# Level_Shifters.net
KiCad netlist of a schematic drawn in Altium Designer
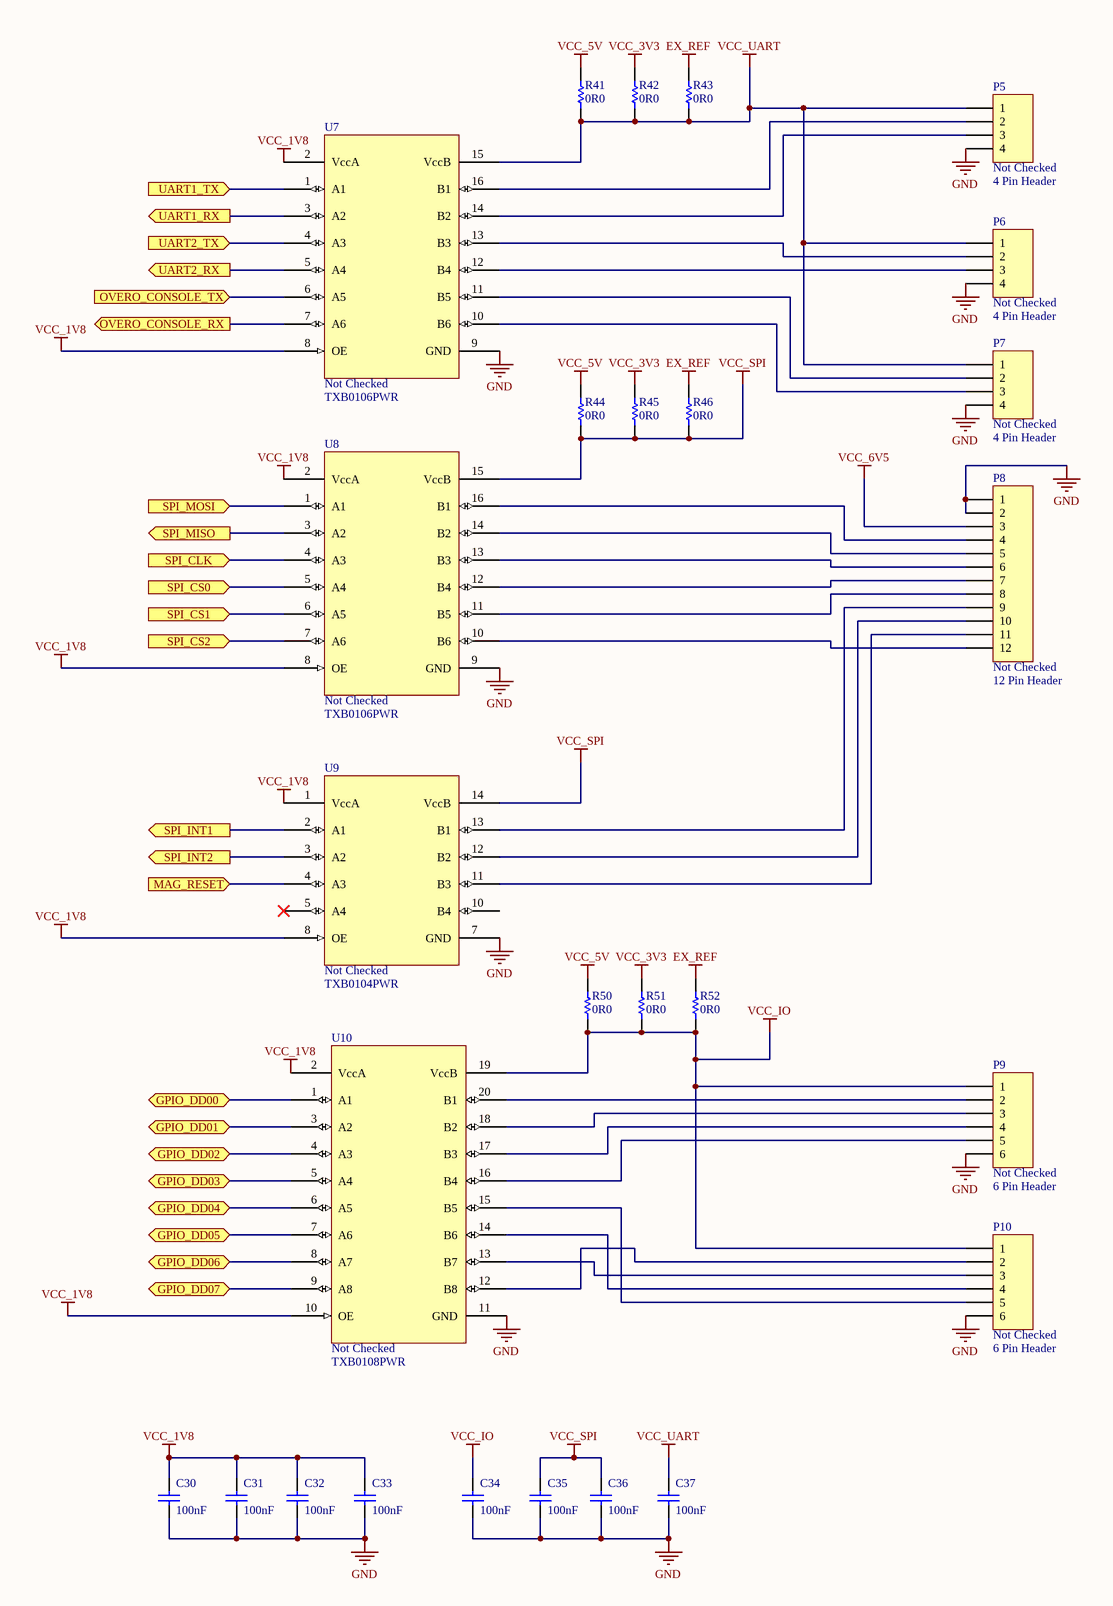
[diagram p0: Level Shifters.SchDoc]

(export (version "E")
  (design (tool "Eeschema 10.0.6"))
  (components
    (comp (ref "C30")
      (value "100nF")
      (footprint "GRC PCB library:0603")
      (description "CAP CER .10UF 50V X5R 0603")
      (fields (field (name "MANUFACTURER") "Taiyo Yuden"))
      (libsource (lib "GRC sch library") (part "CP_100nF 0603"))
    )
    (comp (ref "C31")
      (value "100nF")
      (footprint "GRC PCB library:0603")
      (description "CAP CER .10UF 50V X5R 0603")
      (fields (field (name "MANUFACTURER") "Taiyo Yuden"))
      (libsource (lib "GRC sch library") (part "CP_100nF 0603"))
    )
    (comp (ref "C32")
      (value "100nF")
      (footprint "GRC PCB library:0603")
      (description "CAP CER .10UF 50V X5R 0603")
      (fields (field (name "MANUFACTURER") "Taiyo Yuden"))
      (libsource (lib "GRC sch library") (part "CP_100nF 0603"))
    )
    (comp (ref "C33")
      (value "100nF")
      (footprint "GRC PCB library:0603")
      (description "CAP CER .10UF 50V X5R 0603")
      (fields (field (name "MANUFACTURER") "Taiyo Yuden"))
      (libsource (lib "GRC sch library") (part "CP_100nF 0603"))
    )
    (comp (ref "C34")
      (value "100nF")
      (footprint "GRC PCB library:0603")
      (description "CAP CER .10UF 50V X5R 0603")
      (fields (field (name "MANUFACTURER") "Taiyo Yuden"))
      (libsource (lib "GRC sch library") (part "CP_100nF 0603"))
    )
    (comp (ref "C35")
      (value "100nF")
      (footprint "GRC PCB library:0603")
      (description "CAP CER .10UF 50V X5R 0603")
      (fields (field (name "MANUFACTURER") "Taiyo Yuden"))
      (libsource (lib "GRC sch library") (part "CP_100nF 0603"))
    )
    (comp (ref "C36")
      (value "100nF")
      (footprint "GRC PCB library:0603")
      (description "CAP CER .10UF 50V X5R 0603")
      (fields (field (name "MANUFACTURER") "Taiyo Yuden"))
      (libsource (lib "GRC sch library") (part "CP_100nF 0603"))
    )
    (comp (ref "C37")
      (value "100nF")
      (footprint "GRC PCB library:0603")
      (description "CAP CER .10UF 50V X5R 0603")
      (fields (field (name "MANUFACTURER") "Taiyo Yuden"))
      (libsource (lib "GRC sch library") (part "CP_100nF 0603"))
    )
    (comp (ref "P5")
      (value "4 Pin Header")
      (footprint "CONN_4X1_SMT_RA_1.25MM")
      (description "CONN HDR VERT 4POS .100\" SNGL")
      (fields (field (name "MANUFACTURER") "Molex") (field (name "VERIFY") "Not Checked"))
      (libsource (lib "checked") (part "JP_4PIN HDR_SMT_RA_MOLEX"))
    )
    (comp (ref "P6")
      (value "4 Pin Header")
      (footprint "CONN_4X1_SMT_RA_1.25MM")
      (description "CONN HDR VERT 4POS .100\" SNGL")
      (fields (field (name "MANUFACTURER") "Molex") (field (name "VERIFY") "Not Checked"))
      (libsource (lib "checked") (part "JP_4PIN HDR_SMT_RA_MOLEX"))
    )
    (comp (ref "P7")
      (value "4 Pin Header")
      (footprint "CONN_4X1_SMT_RA_1.25MM")
      (description "CONN HDR VERT 4POS .100\" SNGL")
      (fields (field (name "MANUFACTURER") "Molex") (field (name "VERIFY") "Not Checked"))
      (libsource (lib "checked") (part "JP_4PIN HDR_SMT_RA_MOLEX"))
    )
    (comp (ref "P8")
      (value "12 Pin Header")
      (footprint "CONN_12X1_SMT_RA_1.25MM")
      (description "CONN HDR VERT 12POS .100\" SNGL")
      (fields (field (name "MANUFACTURER") "Molex") (field (name "VERIFY") "Not Checked"))
      (libsource (lib "checked") (part "JP_12PIN HDR_SMT_RA_MOLEX"))
    )
    (comp (ref "P9")
      (value "6 Pin Header")
      (footprint "CONN_6X1_SMT_RA_1.25MM")
      (description "CONN HDR VERT 6POS .100\" SNGL")
      (fields (field (name "MANUFACTURER") "Molex") (field (name "VERIFY") "Not Checked"))
      (libsource (lib "checked") (part "JP_6PIN HDR_SMT_RA_MOLEX"))
    )
    (comp (ref "P10")
      (value "6 Pin Header")
      (footprint "CONN_6X1_SMT_RA_1.25MM")
      (description "CONN HDR VERT 6POS .100\" SNGL")
      (fields (field (name "MANUFACTURER") "Molex") (field (name "VERIFY") "Not Checked"))
      (libsource (lib "checked") (part "JP_6PIN HDR_SMT_RA_MOLEX"))
    )
    (comp (ref "R41")
      (value "0R0")
      (footprint "GRC PCB library:0603")
      (description "RES 0.0 OHM 1/10W 5% 0603 SMD")
      (fields (field (name "MANUFACTURER") "Rohm"))
      (libsource (lib "GRC sch library") (part "RS_0R0 0603"))
    )
    (comp (ref "R42")
      (value "0R0")
      (footprint "GRC PCB library:0603")
      (description "RES 0.0 OHM 1/10W 5% 0603 SMD")
      (fields (field (name "MANUFACTURER") "Rohm"))
      (libsource (lib "GRC sch library") (part "RS_0R0 0603"))
    )
    (comp (ref "R43")
      (value "0R0")
      (footprint "GRC PCB library:0603")
      (description "RES 0.0 OHM 1/10W 5% 0603 SMD")
      (fields (field (name "MANUFACTURER") "Rohm"))
      (libsource (lib "GRC sch library") (part "RS_0R0 0603"))
    )
    (comp (ref "R44")
      (value "0R0")
      (footprint "GRC PCB library:0603")
      (description "RES 0.0 OHM 1/10W 5% 0603 SMD")
      (fields (field (name "MANUFACTURER") "Rohm"))
      (libsource (lib "GRC sch library") (part "RS_0R0 0603"))
    )
    (comp (ref "R45")
      (value "0R0")
      (footprint "GRC PCB library:0603")
      (description "RES 0.0 OHM 1/10W 5% 0603 SMD")
      (fields (field (name "MANUFACTURER") "Rohm"))
      (libsource (lib "GRC sch library") (part "RS_0R0 0603"))
    )
    (comp (ref "R46")
      (value "0R0")
      (footprint "GRC PCB library:0603")
      (description "RES 0.0 OHM 1/10W 5% 0603 SMD")
      (fields (field (name "MANUFACTURER") "Rohm"))
      (libsource (lib "GRC sch library") (part "RS_0R0 0603"))
    )
    (comp (ref "R50")
      (value "0R0")
      (footprint "GRC PCB library:0603")
      (description "RES 0.0 OHM 1/10W 5% 0603 SMD")
      (fields (field (name "MANUFACTURER") "Rohm"))
      (libsource (lib "GRC sch library") (part "RS_0R0 0603"))
    )
    (comp (ref "R51")
      (value "0R0")
      (footprint "GRC PCB library:0603")
      (description "RES 0.0 OHM 1/10W 5% 0603 SMD")
      (fields (field (name "MANUFACTURER") "Rohm"))
      (libsource (lib "GRC sch library") (part "RS_0R0 0603"))
    )
    (comp (ref "R52")
      (value "0R0")
      (footprint "GRC PCB library:0603")
      (description "RES 0.0 OHM 1/10W 5% 0603 SMD")
      (fields (field (name "MANUFACTURER") "Rohm"))
      (libsource (lib "GRC sch library") (part "RS_0R0 0603"))
    )
    (comp (ref "U7")
      (value "TXB0106PWR")
      (footprint "TSSOP-16_PW")
      (description "IC VOLT-LEVEL TRANSLATOR 16TSSOP")
      (fields
        (field (name "MANUFACTURER") "Texas Instruments")
        (field (name "VERIFY") "Not Checked")
        (field (name "Comment") "IC_TXB0106PWR")
      )
      (libsource (lib "checked") (part "IC_TXB0106PWR"))
    )
    (comp (ref "U8")
      (value "TXB0106PWR")
      (footprint "TSSOP-16_PW")
      (description "IC VOLT-LEVEL TRANSLATOR 16TSSOP")
      (fields
        (field (name "MANUFACTURER") "Texas Instruments")
        (field (name "VERIFY") "Not Checked")
        (field (name "Comment") "IC_TXB0106PWR")
      )
      (libsource (lib "checked") (part "IC_TXB0106PWR"))
    )
    (comp (ref "U9")
      (value "TXB0104PWR")
      (footprint "TSSOP-14_PW")
      (description "IC VOLT-LEVEL TRANSLATOR 14TSSOP")
      (fields
        (field (name "MANUFACTURER") "Texas Instruments")
        (field (name "VERIFY") "Not Checked")
        (field (name "Comment") "IC_TXB0104PWR")
      )
      (libsource (lib "checked") (part "IC_TXB0104PWR"))
    )
    (comp (ref "U10")
      (value "TXB0108PWR")
      (footprint "TSSOP-20_PW")
      (description "IC VOLT-LEVEL TRANSLATOR 20TSSOP")
      (fields
        (field (name "MANUFACTURER") "Texas Instruments")
        (field (name "VERIFY") "Not Checked")
        (field (name "Comment") "IC_TXB0108PWR")
      )
      (libsource (lib "checked") (part "IC_TXB0108PWR"))
    )
  )
  (nets
    (net (code "1") (name "/GPIO_DD00") (class "Default")
      (node (ref "U10") (pin "1") (pinfunction "A1_1") (pintype "bidirectional"))
    )
    (net (code "2") (name "/GPIO_DD01") (class "Default")
      (node (ref "U10") (pin "3") (pinfunction "A2_3") (pintype "bidirectional"))
    )
    (net (code "3") (name "/GPIO_DD02") (class "Default")
      (node (ref "U10") (pin "4") (pinfunction "A3_4") (pintype "bidirectional"))
    )
    (net (code "4") (name "/GPIO_DD03") (class "Default")
      (node (ref "U10") (pin "5") (pinfunction "A4_5") (pintype "bidirectional"))
    )
    (net (code "5") (name "/GPIO_DD04") (class "Default")
      (node (ref "U10") (pin "6") (pinfunction "A5_6") (pintype "bidirectional"))
    )
    (net (code "6") (name "/GPIO_DD05") (class "Default")
      (node (ref "U10") (pin "7") (pinfunction "A6_7") (pintype "bidirectional"))
    )
    (net (code "7") (name "/GPIO_DD06") (class "Default")
      (node (ref "U10") (pin "8") (pinfunction "A7_8") (pintype "bidirectional"))
    )
    (net (code "8") (name "/GPIO_DD07") (class "Default")
      (node (ref "U10") (pin "9") (pinfunction "A8_9") (pintype "bidirectional"))
    )
    (net (code "9") (name "/MAG_RESET") (class "Default")
      (node (ref "U9") (pin "4") (pinfunction "A3_4") (pintype "bidirectional"))
    )
    (net (code "10") (name "/OVERO_CONSOLE_RX") (class "Default")
      (node (ref "U7") (pin "7") (pinfunction "A6_7") (pintype "bidirectional"))
    )
    (net (code "11") (name "/OVERO_CONSOLE_TX") (class "Default")
      (node (ref "U7") (pin "6") (pinfunction "A5_6") (pintype "bidirectional"))
    )
    (net (code "12") (name "/SPI_CLK") (class "Default")
      (node (ref "U8") (pin "4") (pinfunction "A3_4") (pintype "bidirectional"))
    )
    (net (code "13") (name "/SPI_CS0") (class "Default")
      (node (ref "U8") (pin "5") (pinfunction "A4_5") (pintype "bidirectional"))
    )
    (net (code "14") (name "/SPI_CS1") (class "Default")
      (node (ref "U8") (pin "6") (pinfunction "A5_6") (pintype "bidirectional"))
    )
    (net (code "15") (name "/SPI_CS2") (class "Default")
      (node (ref "U8") (pin "7") (pinfunction "A6_7") (pintype "bidirectional"))
    )
    (net (code "16") (name "/SPI_INT1") (class "Default")
      (node (ref "U9") (pin "2") (pinfunction "A1_2") (pintype "bidirectional"))
    )
    (net (code "17") (name "/SPI_INT2") (class "Default")
      (node (ref "U9") (pin "3") (pinfunction "A2_3") (pintype "bidirectional"))
    )
    (net (code "18") (name "/SPI_MISO") (class "Default")
      (node (ref "U8") (pin "3") (pinfunction "A2_3") (pintype "bidirectional"))
    )
    (net (code "19") (name "/SPI_MOSI") (class "Default")
      (node (ref "U8") (pin "1") (pinfunction "A1_1") (pintype "bidirectional"))
    )
    (net (code "20") (name "/UART1_RX") (class "Default")
      (node (ref "U7") (pin "3") (pinfunction "A2_3") (pintype "bidirectional"))
    )
    (net (code "21") (name "/UART1_TX") (class "Default")
      (node (ref "U7") (pin "1") (pinfunction "A1_1") (pintype "bidirectional"))
    )
    (net (code "22") (name "/UART2_RX") (class "Default")
      (node (ref "U7") (pin "5") (pinfunction "A4_5") (pintype "bidirectional"))
    )
    (net (code "23") (name "/UART2_TX") (class "Default")
      (node (ref "U7") (pin "4") (pinfunction "A3_4") (pintype "bidirectional"))
    )
    (net (code "24") (name "EX_REF") (class "Default")
      (node (ref "R43") (pin "1") (pinfunction "1_1") (pintype "passive"))
      (node (ref "R46") (pin "1") (pinfunction "1_1") (pintype "passive"))
      (node (ref "R52") (pin "1") (pinfunction "1_1") (pintype "passive"))
    )
    (net (code "25") (name "GND") (class "Default")
      (node (ref "C30") (pin "1") (pinfunction "1_1") (pintype "passive"))
      (node (ref "C31") (pin "1") (pinfunction "1_1") (pintype "passive"))
      (node (ref "C32") (pin "1") (pinfunction "1_1") (pintype "passive"))
      (node (ref "C33") (pin "1") (pinfunction "1_1") (pintype "passive"))
      (node (ref "C34") (pin "1") (pinfunction "1_1") (pintype "passive"))
      (node (ref "C35") (pin "1") (pinfunction "1_1") (pintype "passive"))
      (node (ref "C36") (pin "1") (pinfunction "1_1") (pintype "passive"))
      (node (ref "C37") (pin "1") (pinfunction "1_1") (pintype "passive"))
      (node (ref "P10") (pin "6") (pinfunction "6_6") (pintype "passive"))
      (node (ref "P5") (pin "4") (pinfunction "4_4") (pintype "passive"))
      (node (ref "P6") (pin "4") (pinfunction "4_4") (pintype "passive"))
      (node (ref "P7") (pin "4") (pinfunction "4_4") (pintype "passive"))
      (node (ref "P8") (pin "1") (pinfunction "1_1") (pintype "passive"))
      (node (ref "P8") (pin "2") (pinfunction "2_2") (pintype "passive"))
      (node (ref "P9") (pin "6") (pinfunction "6_6") (pintype "passive"))
      (node (ref "U10") (pin "11") (pinfunction "GND_11") (pintype "power_in"))
      (node (ref "U7") (pin "9") (pinfunction "GND_9") (pintype "power_in"))
      (node (ref "U8") (pin "9") (pinfunction "GND_9") (pintype "power_in"))
      (node (ref "U9") (pin "7") (pinfunction "GND_7") (pintype "power_in"))
    )
    (net (code "26") (name "Net-(U7-B1)") (class "Default")
      (node (ref "P5") (pin "2") (pinfunction "2_2") (pintype "passive"))
      (node (ref "U7") (pin "16") (pinfunction "B1_16") (pintype "bidirectional"))
    )
    (net (code "27") (name "Net-(U7-B2)") (class "Default")
      (node (ref "P5") (pin "3") (pinfunction "3_3") (pintype "passive"))
      (node (ref "U7") (pin "14") (pinfunction "B2_14") (pintype "bidirectional"))
    )
    (net (code "28") (name "Net-(U7-B3)") (class "Default")
      (node (ref "P6") (pin "2") (pinfunction "2_2") (pintype "passive"))
      (node (ref "U7") (pin "13") (pinfunction "B3_13") (pintype "bidirectional"))
    )
    (net (code "29") (name "Net-(U7-B4)") (class "Default")
      (node (ref "P6") (pin "3") (pinfunction "3_3") (pintype "passive"))
      (node (ref "U7") (pin "12") (pinfunction "B4_12") (pintype "bidirectional"))
    )
    (net (code "30") (name "Net-(U7-B5)") (class "Default")
      (node (ref "P7") (pin "2") (pinfunction "2_2") (pintype "passive"))
      (node (ref "U7") (pin "11") (pinfunction "B5_11") (pintype "bidirectional"))
    )
    (net (code "31") (name "Net-(U7-B6)") (class "Default")
      (node (ref "P7") (pin "3") (pinfunction "3_3") (pintype "passive"))
      (node (ref "U7") (pin "10") (pinfunction "B6_10") (pintype "bidirectional"))
    )
    (net (code "32") (name "Net-(U8-B1)") (class "Default")
      (node (ref "P8") (pin "4") (pinfunction "4_4") (pintype "passive"))
      (node (ref "U8") (pin "16") (pinfunction "B1_16") (pintype "bidirectional"))
    )
    (net (code "33") (name "Net-(U8-B2)") (class "Default")
      (node (ref "P8") (pin "5") (pinfunction "5_5") (pintype "passive"))
      (node (ref "U8") (pin "14") (pinfunction "B2_14") (pintype "bidirectional"))
    )
    (net (code "34") (name "Net-(U8-B3)") (class "Default")
      (node (ref "P8") (pin "6") (pinfunction "6_6") (pintype "passive"))
      (node (ref "U8") (pin "13") (pinfunction "B3_13") (pintype "bidirectional"))
    )
    (net (code "35") (name "Net-(U8-B4)") (class "Default")
      (node (ref "P8") (pin "7") (pinfunction "7_7") (pintype "passive"))
      (node (ref "U8") (pin "12") (pinfunction "B4_12") (pintype "bidirectional"))
    )
    (net (code "36") (name "Net-(U8-B5)") (class "Default")
      (node (ref "P8") (pin "8") (pinfunction "8_8") (pintype "passive"))
      (node (ref "U8") (pin "11") (pinfunction "B5_11") (pintype "bidirectional"))
    )
    (net (code "37") (name "Net-(U8-B6)") (class "Default")
      (node (ref "P8") (pin "12") (pinfunction "12_12") (pintype "passive"))
      (node (ref "U8") (pin "10") (pinfunction "B6_10") (pintype "bidirectional"))
    )
    (net (code "38") (name "Net-(U9-B1)") (class "Default")
      (node (ref "P8") (pin "9") (pinfunction "9_9") (pintype "passive"))
      (node (ref "U9") (pin "13") (pinfunction "B1_13") (pintype "bidirectional"))
    )
    (net (code "39") (name "Net-(U9-B2)") (class "Default")
      (node (ref "P8") (pin "10") (pinfunction "10_10") (pintype "passive"))
      (node (ref "U9") (pin "12") (pinfunction "B2_12") (pintype "bidirectional"))
    )
    (net (code "40") (name "Net-(U9-B3)") (class "Default")
      (node (ref "P8") (pin "11") (pinfunction "11_11") (pintype "passive"))
      (node (ref "U9") (pin "11") (pinfunction "B3_11") (pintype "bidirectional"))
    )
    (net (code "41") (name "Net-(U10-B1)") (class "Default")
      (node (ref "P9") (pin "2") (pinfunction "2_2") (pintype "passive"))
      (node (ref "U10") (pin "20") (pinfunction "B1_20") (pintype "bidirectional"))
    )
    (net (code "42") (name "Net-(U10-B2)") (class "Default")
      (node (ref "P9") (pin "3") (pinfunction "3_3") (pintype "passive"))
      (node (ref "U10") (pin "18") (pinfunction "B2_18") (pintype "bidirectional"))
    )
    (net (code "43") (name "Net-(U10-B3)") (class "Default")
      (node (ref "P9") (pin "4") (pinfunction "4_4") (pintype "passive"))
      (node (ref "U10") (pin "17") (pinfunction "B3_17") (pintype "bidirectional"))
    )
    (net (code "44") (name "Net-(U10-B4)") (class "Default")
      (node (ref "P9") (pin "5") (pinfunction "5_5") (pintype "passive"))
      (node (ref "U10") (pin "16") (pinfunction "B4_16") (pintype "bidirectional"))
    )
    (net (code "45") (name "Net-(U10-B5)") (class "Default")
      (node (ref "P10") (pin "5") (pinfunction "5_5") (pintype "passive"))
      (node (ref "U10") (pin "15") (pinfunction "B5_15") (pintype "bidirectional"))
    )
    (net (code "46") (name "Net-(U10-B6)") (class "Default")
      (node (ref "P10") (pin "4") (pinfunction "4_4") (pintype "passive"))
      (node (ref "U10") (pin "14") (pinfunction "B6_14") (pintype "bidirectional"))
    )
    (net (code "47") (name "Net-(U10-B7)") (class "Default")
      (node (ref "P10") (pin "3") (pinfunction "3_3") (pintype "passive"))
      (node (ref "U10") (pin "13") (pinfunction "B7_13") (pintype "bidirectional"))
    )
    (net (code "48") (name "Net-(U10-B8)") (class "Default")
      (node (ref "P10") (pin "2") (pinfunction "2_2") (pintype "passive"))
      (node (ref "U10") (pin "12") (pinfunction "B8_12") (pintype "bidirectional"))
    )
    (net (code "49") (name "VCC_1V8") (class "Default")
      (node (ref "C30") (pin "2") (pinfunction "2_2") (pintype "passive"))
      (node (ref "C31") (pin "2") (pinfunction "2_2") (pintype "passive"))
      (node (ref "C32") (pin "2") (pinfunction "2_2") (pintype "passive"))
      (node (ref "C33") (pin "2") (pinfunction "2_2") (pintype "passive"))
      (node (ref "U10") (pin "10") (pinfunction "OE_10") (pintype "input"))
      (node (ref "U10") (pin "2") (pinfunction "VccA_2") (pintype "power_in"))
      (node (ref "U7") (pin "2") (pinfunction "VccA_2") (pintype "power_in"))
      (node (ref "U7") (pin "8") (pinfunction "OE_8") (pintype "input"))
      (node (ref "U8") (pin "2") (pinfunction "VccA_2") (pintype "power_in"))
      (node (ref "U8") (pin "8") (pinfunction "OE_8") (pintype "input"))
      (node (ref "U9") (pin "1") (pinfunction "VccA_1") (pintype "power_in"))
      (node (ref "U9") (pin "8") (pinfunction "OE_8") (pintype "input"))
    )
    (net (code "50") (name "VCC_3V3") (class "Default")
      (node (ref "R42") (pin "1") (pinfunction "1_1") (pintype "passive"))
      (node (ref "R45") (pin "1") (pinfunction "1_1") (pintype "passive"))
      (node (ref "R51") (pin "1") (pinfunction "1_1") (pintype "passive"))
    )
    (net (code "51") (name "VCC_5V") (class "Default")
      (node (ref "R41") (pin "1") (pinfunction "1_1") (pintype "passive"))
      (node (ref "R44") (pin "1") (pinfunction "1_1") (pintype "passive"))
      (node (ref "R50") (pin "1") (pinfunction "1_1") (pintype "passive"))
    )
    (net (code "52") (name "VCC_6V5") (class "Default")
      (node (ref "P8") (pin "3") (pinfunction "3_3") (pintype "passive"))
    )
    (net (code "53") (name "VCC_IO") (class "Default")
      (node (ref "C34") (pin "2") (pinfunction "2_2") (pintype "passive"))
      (node (ref "P10") (pin "1") (pinfunction "1_1") (pintype "passive"))
      (node (ref "P9") (pin "1") (pinfunction "1_1") (pintype "passive"))
      (node (ref "R50") (pin "2") (pinfunction "2_2") (pintype "passive"))
      (node (ref "R51") (pin "2") (pinfunction "2_2") (pintype "passive"))
      (node (ref "R52") (pin "2") (pinfunction "2_2") (pintype "passive"))
      (node (ref "U10") (pin "19") (pinfunction "VccB_19") (pintype "power_in"))
    )
    (net (code "54") (name "VCC_SPI") (class "Default")
      (node (ref "C35") (pin "2") (pinfunction "2_2") (pintype "passive"))
      (node (ref "C36") (pin "2") (pinfunction "2_2") (pintype "passive"))
      (node (ref "R44") (pin "2") (pinfunction "2_2") (pintype "passive"))
      (node (ref "R45") (pin "2") (pinfunction "2_2") (pintype "passive"))
      (node (ref "R46") (pin "2") (pinfunction "2_2") (pintype "passive"))
      (node (ref "U8") (pin "15") (pinfunction "VccB_15") (pintype "power_in"))
      (node (ref "U9") (pin "14") (pinfunction "VccB_14") (pintype "power_in"))
    )
    (net (code "55") (name "VCC_UART") (class "Default")
      (node (ref "C37") (pin "2") (pinfunction "2_2") (pintype "passive"))
      (node (ref "P5") (pin "1") (pinfunction "1_1") (pintype "passive"))
      (node (ref "P6") (pin "1") (pinfunction "1_1") (pintype "passive"))
      (node (ref "P7") (pin "1") (pinfunction "1_1") (pintype "passive"))
      (node (ref "R41") (pin "2") (pinfunction "2_2") (pintype "passive"))
      (node (ref "R42") (pin "2") (pinfunction "2_2") (pintype "passive"))
      (node (ref "R43") (pin "2") (pinfunction "2_2") (pintype "passive"))
      (node (ref "U7") (pin "15") (pinfunction "VccB_15") (pintype "power_in"))
    )
    (net (code "56") (name "unconnected-(U9-A4-Pad5)") (class "Default")
      (node (ref "U9") (pin "5") (pinfunction "A4_5") (pintype "bidirectional+no_connect"))
    )
    (net (code "57") (name "unconnected-(U9-B4-Pad10)") (class "Default")
      (node (ref "U9") (pin "10") (pinfunction "B4_10") (pintype "bidirectional"))
    )
  )
)
